# RPi.net
KiCad netlist of a schematic drawn in EAGLE
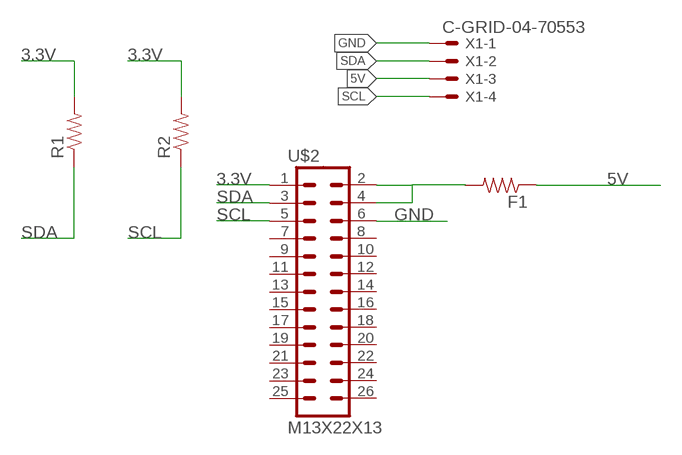
[diagram p0: schematic, sheet 1]

(export (version "E")
  (design (tool "Eeschema 10.0.6"))
  (components
    (comp (ref "F1")
      (value "RESISTOR0805-RES")
      (footprint "eagle-import:0805")
      (libsource (lib "eagle-import") (part "RESISTOR0805-RES"))
    )
    (comp (ref "R1")
      (value "RESISTOR0805-RES")
      (footprint "eagle-import:0805")
      (libsource (lib "eagle-import") (part "RESISTOR0805-RES"))
    )
    (comp (ref "R2")
      (value "RESISTOR0805-RES")
      (footprint "eagle-import:0805")
      (libsource (lib "eagle-import") (part "RESISTOR0805-RES"))
    )
    (comp (ref "U$2")
      (value "M13X22X13")
      (footprint "eagle-import:2X13")
      (libsource (lib "eagle-import") (part "M13X22X13"))
    )
    (comp (ref "X1")
      (value "C-GRID-04-70553")
      (footprint "eagle-import:70553-04")
      (libsource (lib "eagle-import") (part "C-GRID-04-70553"))
    )
  )
  (nets
    (net (code "1") (name "/3.3V") (class "Default")
      (node (ref "R1") (pin "2") (pinfunction "2_2") (pintype "passive"))
      (node (ref "R2") (pin "2") (pinfunction "2_2") (pintype "passive"))
      (node (ref "U$2") (pin "1") (pinfunction "1_1") (pintype "passive"))
    )
    (net (code "2") (name "5V") (class "Default")
      (node (ref "F1") (pin "1") (pinfunction "1_1") (pintype "passive"))
      (node (ref "X1") (pin "3") (pinfunction "S_3") (pintype "passive"))
    )
    (net (code "3") (name "GND") (class "Default")
      (node (ref "U$2") (pin "6") (pinfunction "6_6") (pintype "passive"))
      (node (ref "X1") (pin "1") (pinfunction "S_1") (pintype "passive"))
    )
    (net (code "4") (name "Net-(F1-Pad2)") (class "Default")
      (node (ref "F1") (pin "2") (pinfunction "2_2") (pintype "passive"))
      (node (ref "U$2") (pin "2") (pinfunction "2_2") (pintype "passive"))
      (node (ref "U$2") (pin "4") (pinfunction "4_4") (pintype "passive"))
    )
    (net (code "5") (name "SCL") (class "Default")
      (node (ref "R2") (pin "1") (pinfunction "1_1") (pintype "passive"))
      (node (ref "U$2") (pin "5") (pinfunction "5_5") (pintype "passive"))
      (node (ref "X1") (pin "4") (pinfunction "S_4") (pintype "passive"))
    )
    (net (code "6") (name "SDA") (class "Default")
      (node (ref "R1") (pin "1") (pinfunction "1_1") (pintype "passive"))
      (node (ref "U$2") (pin "3") (pinfunction "3_3") (pintype "passive"))
      (node (ref "X1") (pin "2") (pinfunction "S_2") (pintype "passive"))
    )
    (net (code "7") (name "unconnected-(U$2-Pad7)") (class "Default")
      (node (ref "U$2") (pin "7") (pinfunction "7_7") (pintype "passive"))
    )
    (net (code "8") (name "unconnected-(U$2-Pad8)") (class "Default")
      (node (ref "U$2") (pin "8") (pinfunction "8_8") (pintype "passive"))
    )
    (net (code "9") (name "unconnected-(U$2-Pad9)") (class "Default")
      (node (ref "U$2") (pin "9") (pinfunction "9_9") (pintype "passive"))
    )
    (net (code "10") (name "unconnected-(U$2-Pad10)") (class "Default")
      (node (ref "U$2") (pin "10") (pinfunction "10_10") (pintype "passive"))
    )
    (net (code "11") (name "unconnected-(U$2-Pad11)") (class "Default")
      (node (ref "U$2") (pin "11") (pinfunction "11_11") (pintype "passive"))
    )
    (net (code "12") (name "unconnected-(U$2-Pad12)") (class "Default")
      (node (ref "U$2") (pin "12") (pinfunction "12_12") (pintype "passive"))
    )
    (net (code "13") (name "unconnected-(U$2-Pad13)") (class "Default")
      (node (ref "U$2") (pin "13") (pinfunction "13_13") (pintype "passive"))
    )
    (net (code "14") (name "unconnected-(U$2-Pad14)") (class "Default")
      (node (ref "U$2") (pin "14") (pinfunction "14_14") (pintype "passive"))
    )
    (net (code "15") (name "unconnected-(U$2-Pad15)") (class "Default")
      (node (ref "U$2") (pin "15") (pinfunction "15_15") (pintype "passive"))
    )
    (net (code "16") (name "unconnected-(U$2-Pad16)") (class "Default")
      (node (ref "U$2") (pin "16") (pinfunction "16_16") (pintype "passive"))
    )
    (net (code "17") (name "unconnected-(U$2-Pad17)") (class "Default")
      (node (ref "U$2") (pin "17") (pinfunction "17_17") (pintype "passive"))
    )
    (net (code "18") (name "unconnected-(U$2-Pad18)") (class "Default")
      (node (ref "U$2") (pin "18") (pinfunction "18_18") (pintype "passive"))
    )
    (net (code "19") (name "unconnected-(U$2-Pad19)") (class "Default")
      (node (ref "U$2") (pin "19") (pinfunction "19_19") (pintype "passive"))
    )
    (net (code "20") (name "unconnected-(U$2-Pad20)") (class "Default")
      (node (ref "U$2") (pin "20") (pinfunction "20_20") (pintype "passive"))
    )
    (net (code "21") (name "unconnected-(U$2-Pad21)") (class "Default")
      (node (ref "U$2") (pin "21") (pinfunction "21_21") (pintype "passive"))
    )
    (net (code "22") (name "unconnected-(U$2-Pad22)") (class "Default")
      (node (ref "U$2") (pin "22") (pinfunction "22_22") (pintype "passive"))
    )
    (net (code "23") (name "unconnected-(U$2-Pad23)") (class "Default")
      (node (ref "U$2") (pin "23") (pinfunction "23_23") (pintype "passive"))
    )
    (net (code "24") (name "unconnected-(U$2-Pad24)") (class "Default")
      (node (ref "U$2") (pin "24") (pinfunction "24_24") (pintype "passive"))
    )
    (net (code "25") (name "unconnected-(U$2-Pad25)") (class "Default")
      (node (ref "U$2") (pin "25") (pinfunction "25_25") (pintype "passive"))
    )
    (net (code "26") (name "unconnected-(U$2-Pad26)") (class "Default")
      (node (ref "U$2") (pin "26") (pinfunction "26_26") (pintype "passive"))
    )
  )
)
